# 16_HDMI_schdoc.net
KiCad netlist of a schematic drawn in Altium Designer
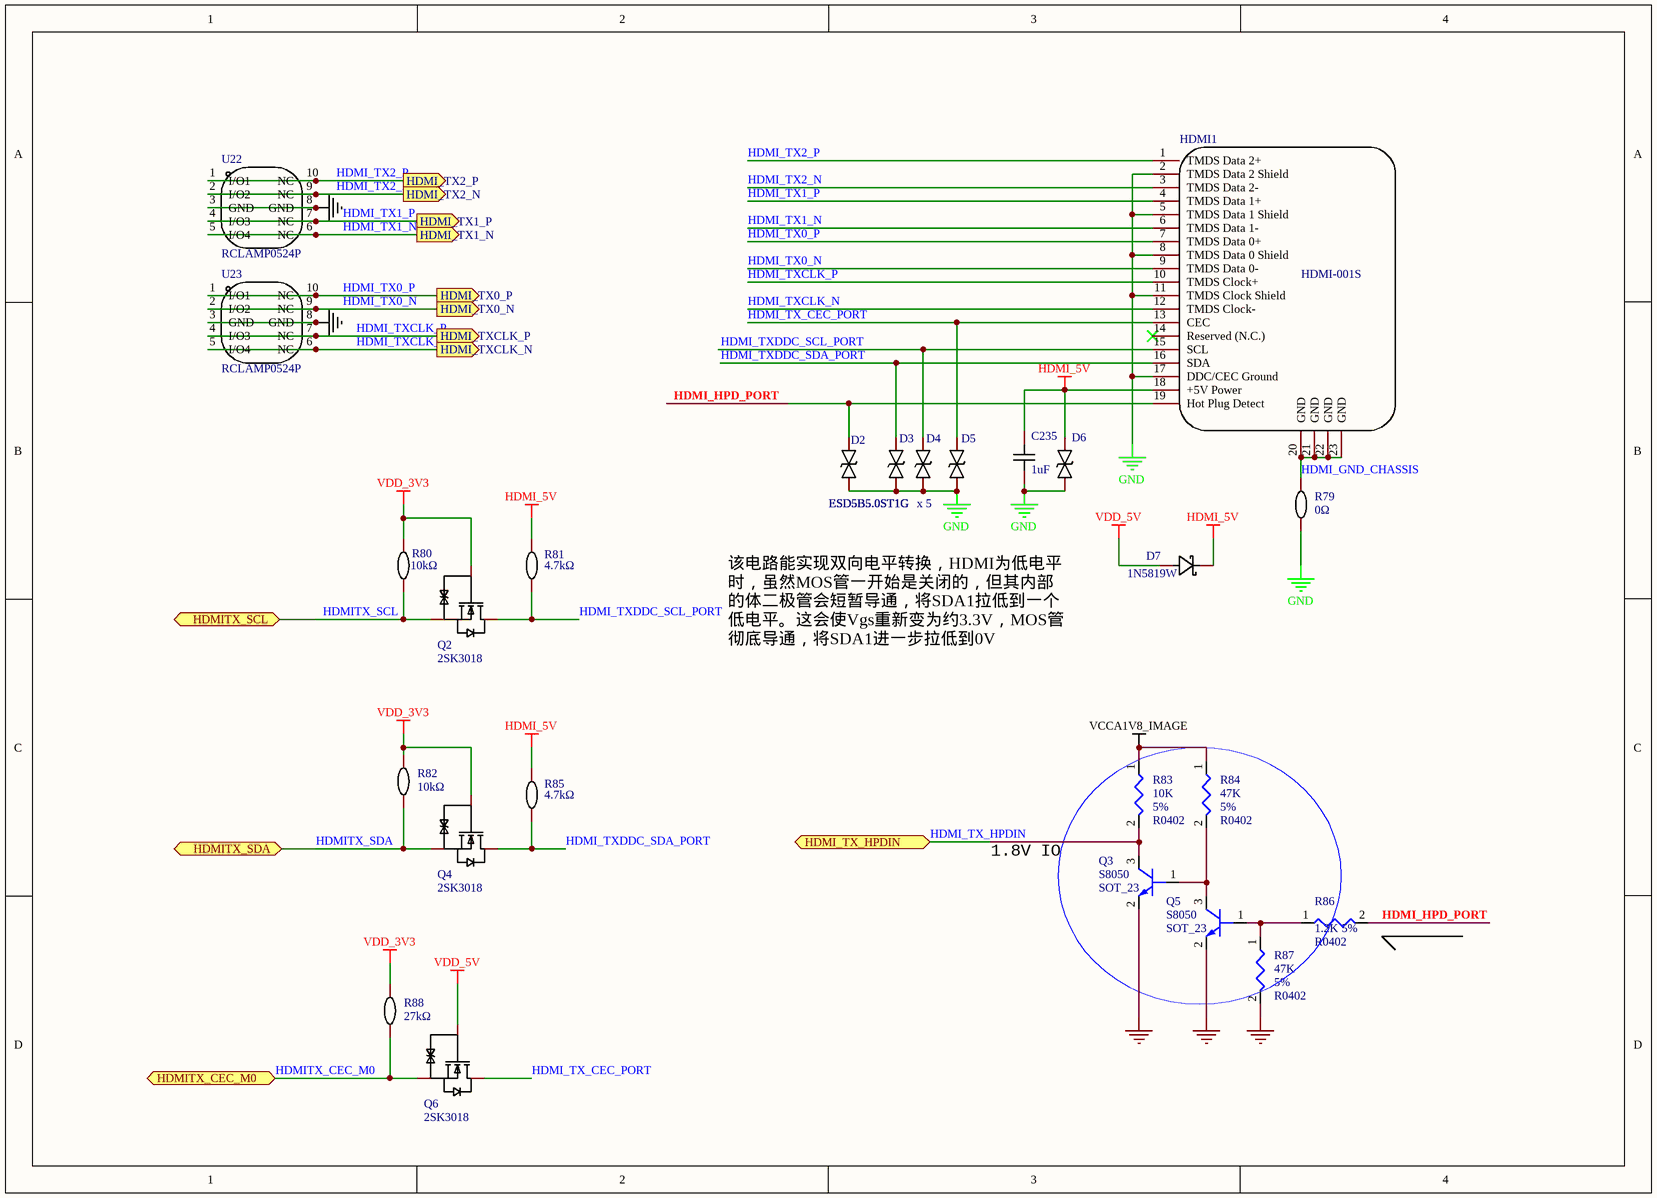
[diagram p0: 16_HDMI接口.schdoc.schdoc]

(export (version "E")
  (design (tool "Eeschema 10.0.6"))
  (components
    (comp (ref "C235")
      (value "1uF")
      (footprint "C0603")
      (fields
        (field (name "NAME") "1uF")
        (field (name "MANUFACTURER") "SAMSUNG(三星)")
        (field (name "MANUFACTURER PART") "CL10A105KB8NNNC")
        (field (name "TOLERANCE") "±10%")
      )
      (libsource (lib "altium-import") (part "root_1_CL10A105KB8NNNC_"))
    )
    (comp (ref "D2")
      (value "ESD5B5.0ST1G")
      (footprint "SOD-523_L1.2-W0.8-LS1.6-BI")
      (fields (field (name "NAME") "ESD5B5.0ST1G") (field (name "MANUFACTURER") "onsemi(安森美)"))
      (libsource (lib "altium-import") (part "root_1_ESD5B5.0ST1G_"))
    )
    (comp (ref "D3")
      (value "ESD5B5.0ST1G")
      (footprint "SOD-523_L1.2-W0.8-LS1.6-BI")
      (fields (field (name "NAME") "ESD5B5.0ST1G") (field (name "MANUFACTURER") "onsemi(安森美)"))
      (libsource (lib "altium-import") (part "root_1_ESD5B5.0ST1G_"))
    )
    (comp (ref "D4")
      (value "ESD5B5.0ST1G")
      (footprint "SOD-523_L1.2-W0.8-LS1.6-BI")
      (fields (field (name "NAME") "ESD5B5.0ST1G") (field (name "MANUFACTURER") "onsemi(安森美)"))
      (libsource (lib "altium-import") (part "root_1_ESD5B5.0ST1G_"))
    )
    (comp (ref "D5")
      (value "ESD5B5.0ST1G")
      (footprint "SOD-523_L1.2-W0.8-LS1.6-BI")
      (fields (field (name "NAME") "ESD5B5.0ST1G") (field (name "MANUFACTURER") "onsemi(安森美)"))
      (libsource (lib "altium-import") (part "root_1_ESD5B5.0ST1G_"))
    )
    (comp (ref "D6")
      (value "ESD5B5.0ST1G")
      (footprint "SOD-523_L1.2-W0.8-LS1.6-BI")
      (fields (field (name "NAME") "ESD5B5.0ST1G") (field (name "MANUFACTURER") "onsemi(安森美)"))
      (libsource (lib "altium-import") (part "root_1_ESD5B5.0ST1G_"))
    )
    (comp (ref "D7")
      (value "1N5819W")
      (footprint "SOD-123_L2.7-W1.6-LS3.7-R-RD")
      (fields (field (name "NAME") "1N5819W") (field (name "MANUFACTURER") "JSMSEMI(杰盛微)"))
      (libsource (lib "altium-import") (part "root_2_1N5819W_C963381_"))
    )
    (comp (ref "HDMI1")
      (value "HDMI-001S")
      (footprint "HDMI-SMD_HDMI-001S")
      (fields (field (name "NAME") "HDMI-001S") (field (name "MANUFACTURER") "XUNPU(讯普)"))
      (libsource (lib "altium-import") (part "root_0_HDMI-001S_"))
    )
    (comp (ref "Q2")
      (value "2SK3018")
      (footprint "SOT-23-3_L2.9-W1.4-P1.90-LS2.6-BR")
      (fields (field (name "NAME") "2SK3018") (field (name "MANUFACTURER") "TWGMC(台湾迪嘉)"))
      (libsource (lib "altium-import") (part "root_3_2SK3018_"))
    )
    (comp (ref "Q3")
      (value "S8050")
      (footprint "SOT_23")
      (description "S8050,SOT23")
      (fields
        (field (name "PCB FOOTPRINT") "SOT_23")
        (field (name "MANUFACTURER") "长电")
        (field (name "CREATED BY") "JJJ")
      )
      (libsource (lib "*") (part "NPN"))
    )
    (comp (ref "Q4")
      (value "2SK3018")
      (footprint "SOT-23-3_L2.9-W1.4-P1.90-LS2.6-BR")
      (fields (field (name "NAME") "2SK3018") (field (name "MANUFACTURER") "TWGMC(台湾迪嘉)"))
      (libsource (lib "altium-import") (part "root_3_2SK3018_"))
    )
    (comp (ref "Q5")
      (value "S8050")
      (footprint "SOT_23")
      (description "S8050,SOT23")
      (fields
        (field (name "PCB FOOTPRINT") "SOT_23")
        (field (name "MANUFACTURER") "长电")
        (field (name "CREATED BY") "JJJ")
      )
      (libsource (lib "*") (part "NPN"))
    )
    (comp (ref "Q6")
      (value "2SK3018")
      (footprint "SOT-23-3_L2.9-W1.4-P1.90-LS2.6-BR")
      (fields (field (name "NAME") "2SK3018") (field (name "MANUFACTURER") "TWGMC(台湾迪嘉)"))
      (libsource (lib "altium-import") (part "root_3_2SK3018_"))
    )
    (comp (ref "R79")
      (value "0Ω")
      (footprint "R0603")
      (fields
        (field (name "NAME") "0Ω")
        (field (name "MANUFACTURER") "UNI-ROYAL(厚声)")
        (field (name "MANUFACTURER PART") "0603WAF0000T5E")
        (field (name "TOLERANCE") "±1%")
      )
      (libsource (lib "altium-import") (part "root_1_0603WAF0000T5E_"))
    )
    (comp (ref "R80")
      (value "10kΩ")
      (footprint "R0603")
      (fields
        (field (name "NAME") "10kΩ")
        (field (name "MANUFACTURER") "UNI-ROYAL(厚声)")
        (field (name "MANUFACTURER PART") "0603WAF1002T5E")
        (field (name "TOLERANCE") "±1%")
      )
      (libsource (lib "altium-import") (part "root_1_0603WAF1002T5E_"))
    )
    (comp (ref "R81")
      (value "4.7kΩ")
      (footprint "R0603")
      (fields
        (field (name "NAME") "4.7kΩ")
        (field (name "MANUFACTURER") "UNI-ROYAL(厚声)")
        (field (name "MANUFACTURER PART") "0603WAF4701T5E")
        (field (name "TOLERANCE") "±1%")
      )
      (libsource (lib "altium-import") (part "root_1_0603WAF4701T5E_"))
    )
    (comp (ref "R82")
      (value "10kΩ")
      (footprint "R0603")
      (fields
        (field (name "NAME") "10kΩ")
        (field (name "MANUFACTURER") "UNI-ROYAL(厚声)")
        (field (name "MANUFACTURER PART") "0603WAF1002T5E")
        (field (name "TOLERANCE") "±1%")
      )
      (libsource (lib "altium-import") (part "root_1_0603WAF1002T5E_"))
    )
    (comp (ref "R83")
      (value "10K")
      (footprint "R0402")
      (description "通用厚膜电阻,10K,+/-5%,R0402,1/16W.")
      (fields
        (field (name "PCB FOOTPRINT") "R0402")
        (field (name "TOLERANCE") "5%")
        (field (name "MANUFACTURER") "YAGEO")
        (field (name "CREATED BY") "YTL")
      )
      (libsource (lib "*") (part "RESISTOR_Dup1"))
    )
    (comp (ref "R84")
      (value "47K")
      (footprint "R0402")
      (description "通用厚膜电阻,47K,+/-5%,R0402,1/16W.")
      (fields
        (field (name "PCB FOOTPRINT") "R0402")
        (field (name "TOLERANCE") "5%")
        (field (name "MANUFACTURER") "YAGEO")
        (field (name "CREATED BY") "YTL")
      )
      (libsource (lib "*") (part "RESISTOR_Dup1"))
    )
    (comp (ref "R85")
      (value "4.7kΩ")
      (footprint "R0603")
      (fields
        (field (name "NAME") "4.7kΩ")
        (field (name "MANUFACTURER") "UNI-ROYAL(厚声)")
        (field (name "MANUFACTURER PART") "0603WAF4701T5E")
        (field (name "TOLERANCE") "±1%")
      )
      (libsource (lib "altium-import") (part "root_1_0603WAF4701T5E_"))
    )
    (comp (ref "R86")
      (value "1.2K")
      (footprint "R0402")
      (description "通用厚膜电阻,1K2,+/-5%,R0402,1/16W.")
      (fields
        (field (name "PCB FOOTPRINT") "R0402")
        (field (name "TOLERANCE") "5%")
        (field (name "MANUFACTURER") "YAGEO")
        (field (name "CREATED BY") "YTL")
      )
      (libsource (lib "*") (part "RESISTOR_Dup1"))
    )
    (comp (ref "R87")
      (value "47K")
      (footprint "R0402")
      (description "通用厚膜电阻,47K,+/-5%,R0402,1/16W.")
      (fields
        (field (name "PCB FOOTPRINT") "R0402")
        (field (name "TOLERANCE") "5%")
        (field (name "MANUFACTURER") "YAGEO")
        (field (name "CREATED BY") "YTL")
      )
      (libsource (lib "*") (part "RESISTOR_Dup1"))
    )
    (comp (ref "R88")
      (value "27kΩ")
      (footprint "R0603")
      (fields
        (field (name "NAME") "27kΩ")
        (field (name "MANUFACTURER") "UNI-ROYAL(厚声)")
        (field (name "MANUFACTURER PART") "0603WAF2702T5E")
        (field (name "TOLERANCE") "±1%")
      )
      (libsource (lib "altium-import") (part "root_1_0603WAF2702T5E_"))
    )
    (comp (ref "U22")
      (value "RCLAMP0524P")
      (footprint "DFN2510-10_L2.5-W1.0-P0.50-BL")
      (fields (field (name "NAME") "RCLAMP0524P") (field (name "MANUFACTURER") "TECH PUBLIC(台舟)"))
      (libsource (lib "altium-import") (part "root_0_RCLAMP0524P_C907837_"))
    )
    (comp (ref "U23")
      (value "RCLAMP0524P")
      (footprint "DFN2510-10_L2.5-W1.0-P0.50-BL")
      (fields (field (name "NAME") "RCLAMP0524P") (field (name "MANUFACTURER") "TECH PUBLIC(台舟)"))
      (libsource (lib "altium-import") (part "root_0_RCLAMP0524P_C907837_"))
    )
  )
  (nets
    (net (code "1") (name "/HDMITX_CEC_M0") (class "Default")
      (node (ref "Q6") (pin "2") (pinfunction "S_2") (pintype "passive"))
      (node (ref "R88") (pin "1") (pinfunction "1_1") (pintype "passive"))
    )
    (net (code "2") (name "/HDMITX_SCL") (class "Default")
      (node (ref "Q2") (pin "2") (pinfunction "S_2") (pintype "passive"))
      (node (ref "R80") (pin "1") (pinfunction "1_1") (pintype "passive"))
    )
    (net (code "3") (name "/HDMITX_SDA") (class "Default")
      (node (ref "Q4") (pin "2") (pinfunction "S_2") (pintype "passive"))
      (node (ref "R82") (pin "1") (pinfunction "1_1") (pintype "passive"))
    )
    (net (code "4") (name "/HDMI_GND_CHASSIS") (class "Default")
      (node (ref "HDMI1") (pin "20") (pinfunction "GND_20") (pintype "passive"))
      (node (ref "HDMI1") (pin "21") (pinfunction "GND_21") (pintype "passive"))
      (node (ref "HDMI1") (pin "22") (pinfunction "GND_22") (pintype "passive"))
      (node (ref "HDMI1") (pin "23") (pinfunction "GND_23") (pintype "passive"))
      (node (ref "R79") (pin "2") (pinfunction "2_2") (pintype "passive"))
    )
    (net (code "5") (name "/HDMI_HPD_PORT") (class "Default")
      (node (ref "D2") (pin "2") (pinfunction "2_2") (pintype "passive"))
      (node (ref "HDMI1") (pin "19") (pinfunction "Hot_Plug_Detect_19") (pintype "passive"))
      (node (ref "R86") (pin "2") (pinfunction "2_2") (pintype "passive"))
    )
    (net (code "6") (name "/HDMI_TX0_N") (class "Default")
      (node (ref "HDMI1") (pin "9") (pinfunction "TMDS_Data_0-_9") (pintype "passive"))
      (node (ref "U23") (pin "2") (pinfunction "I/O2_2") (pintype "passive"))
      (node (ref "U23") (pin "9") (pinfunction "NC_9") (pintype "passive"))
    )
    (net (code "7") (name "/HDMI_TX0_P") (class "Default")
      (node (ref "HDMI1") (pin "7") (pinfunction "TMDS_Data_0+_7") (pintype "passive"))
      (node (ref "U23") (pin "1") (pinfunction "I/O1_1") (pintype "passive"))
      (node (ref "U23") (pin "10") (pinfunction "NC_10") (pintype "passive"))
    )
    (net (code "8") (name "/HDMI_TX1_N") (class "Default")
      (node (ref "HDMI1") (pin "6") (pinfunction "TMDS_Data_1-_6") (pintype "passive"))
      (node (ref "U22") (pin "5") (pinfunction "I/O4_5") (pintype "passive"))
      (node (ref "U22") (pin "6") (pinfunction "NC_6") (pintype "passive"))
    )
    (net (code "9") (name "/HDMI_TX1_P") (class "Default")
      (node (ref "HDMI1") (pin "4") (pinfunction "TMDS_Data_1+_4") (pintype "passive"))
      (node (ref "U22") (pin "4") (pinfunction "I/O3_4") (pintype "passive"))
      (node (ref "U22") (pin "7") (pinfunction "NC_7") (pintype "passive"))
    )
    (net (code "10") (name "/HDMI_TX2_N") (class "Default")
      (node (ref "HDMI1") (pin "3") (pinfunction "TMDS_Data_2-_3") (pintype "passive"))
      (node (ref "U22") (pin "2") (pinfunction "I/O2_2") (pintype "passive"))
      (node (ref "U22") (pin "9") (pinfunction "NC_9") (pintype "passive"))
    )
    (net (code "11") (name "/HDMI_TX2_P") (class "Default")
      (node (ref "HDMI1") (pin "1") (pinfunction "TMDS_Data_2+_1") (pintype "passive"))
      (node (ref "U22") (pin "1") (pinfunction "I/O1_1") (pintype "passive"))
      (node (ref "U22") (pin "10") (pinfunction "NC_10") (pintype "passive"))
    )
    (net (code "12") (name "/HDMI_TXCLK_N") (class "Default")
      (node (ref "HDMI1") (pin "12") (pinfunction "TMDS_Clock-_12") (pintype "passive"))
      (node (ref "U23") (pin "5") (pinfunction "I/O4_5") (pintype "passive"))
      (node (ref "U23") (pin "6") (pinfunction "NC_6") (pintype "passive"))
    )
    (net (code "13") (name "/HDMI_TXCLK_P") (class "Default")
      (node (ref "HDMI1") (pin "10") (pinfunction "TMDS_Clock+_10") (pintype "passive"))
      (node (ref "U23") (pin "4") (pinfunction "I/O3_4") (pintype "passive"))
      (node (ref "U23") (pin "7") (pinfunction "NC_7") (pintype "passive"))
    )
    (net (code "14") (name "/HDMI_TXDDC_SCL_PORT") (class "Default")
      (node (ref "D4") (pin "2") (pinfunction "2_2") (pintype "passive"))
      (node (ref "HDMI1") (pin "15") (pinfunction "SCL_15") (pintype "passive"))
      (node (ref "Q2") (pin "3") (pinfunction "D_3") (pintype "passive"))
      (node (ref "R81") (pin "1") (pinfunction "1_1") (pintype "passive"))
    )
    (net (code "15") (name "/HDMI_TXDDC_SDA_PORT") (class "Default")
      (node (ref "D3") (pin "2") (pinfunction "2_2") (pintype "passive"))
      (node (ref "HDMI1") (pin "16") (pinfunction "SDA_16") (pintype "passive"))
      (node (ref "Q4") (pin "3") (pinfunction "D_3") (pintype "passive"))
      (node (ref "R85") (pin "1") (pinfunction "1_1") (pintype "passive"))
    )
    (net (code "16") (name "/HDMI_TX_CEC_PORT") (class "Default")
      (node (ref "D5") (pin "2") (pinfunction "2_2") (pintype "passive"))
      (node (ref "HDMI1") (pin "13") (pinfunction "CEC_13") (pintype "passive"))
      (node (ref "Q6") (pin "3") (pinfunction "D_3") (pintype "passive"))
    )
    (net (code "17") (name "/HDMI_TX_HPDIN") (class "Default")
      (node (ref "Q3") (pin "3") (pinfunction "COLLECTOR_3") (pintype "passive"))
      (node (ref "R83") (pin "2") (pinfunction "2_2") (pintype "passive"))
    )
    (net (code "18") (name "GND") (class "Default")
      (node (ref "C235") (pin "1") (pinfunction "1_1") (pintype "passive"))
      (node (ref "D2") (pin "1") (pinfunction "1_1") (pintype "passive"))
      (node (ref "D3") (pin "1") (pinfunction "1_1") (pintype "passive"))
      (node (ref "D4") (pin "1") (pinfunction "1_1") (pintype "passive"))
      (node (ref "D5") (pin "1") (pinfunction "1_1") (pintype "passive"))
      (node (ref "D6") (pin "1") (pinfunction "1_1") (pintype "passive"))
      (node (ref "HDMI1") (pin "11") (pinfunction "TMDS_Clock_Shield_11") (pintype "passive"))
      (node (ref "HDMI1") (pin "17") (pinfunction "DDC/CEC_Ground_17") (pintype "passive"))
      (node (ref "HDMI1") (pin "2") (pinfunction "TMDS_Data_2_Shield_2") (pintype "passive"))
      (node (ref "HDMI1") (pin "5") (pinfunction "TMDS_Data_1_Shield_5") (pintype "passive"))
      (node (ref "HDMI1") (pin "8") (pinfunction "TMDS_Data_0_Shield_8") (pintype "passive"))
      (node (ref "Q3") (pin "2") (pinfunction "EMITTER_2") (pintype "passive"))
      (node (ref "Q5") (pin "2") (pinfunction "EMITTER_2") (pintype "passive"))
      (node (ref "R79") (pin "1") (pinfunction "1_1") (pintype "passive"))
      (node (ref "R87") (pin "2") (pinfunction "2_2") (pintype "passive"))
      (node (ref "U22") (pin "3") (pinfunction "GND_3") (pintype "passive"))
      (node (ref "U22") (pin "8") (pinfunction "GND_8") (pintype "passive"))
      (node (ref "U23") (pin "3") (pinfunction "GND_3") (pintype "passive"))
      (node (ref "U23") (pin "8") (pinfunction "GND_8") (pintype "passive"))
    )
    (net (code "19") (name "HDMI_5V") (class "Default")
      (node (ref "C235") (pin "2") (pinfunction "2_2") (pintype "passive"))
      (node (ref "D6") (pin "2") (pinfunction "2_2") (pintype "passive"))
      (node (ref "D7") (pin "2") (pinfunction "C_2") (pintype "passive"))
      (node (ref "HDMI1") (pin "18") (pinfunction "+5V_Power_18") (pintype "passive"))
      (node (ref "R81") (pin "2") (pinfunction "2_2") (pintype "passive"))
      (node (ref "R85") (pin "2") (pinfunction "2_2") (pintype "passive"))
    )
    (net (code "20") (name "Net-(Q3-BASE)") (class "Default")
      (node (ref "Q3") (pin "1") (pinfunction "BASE_1") (pintype "passive"))
      (node (ref "Q5") (pin "3") (pinfunction "COLLECTOR_3") (pintype "passive"))
      (node (ref "R84") (pin "2") (pinfunction "2_2") (pintype "passive"))
    )
    (net (code "21") (name "Net-(Q5-BASE)") (class "Default")
      (node (ref "Q5") (pin "1") (pinfunction "BASE_1") (pintype "passive"))
      (node (ref "R86") (pin "1") (pinfunction "1_1") (pintype "passive"))
      (node (ref "R87") (pin "1") (pinfunction "1_1") (pintype "passive"))
    )
    (net (code "22") (name "VCCA1V8_IMAGE") (class "Default")
      (node (ref "R83") (pin "1") (pinfunction "1_1") (pintype "passive"))
      (node (ref "R84") (pin "1") (pinfunction "1_1") (pintype "passive"))
    )
    (net (code "23") (name "VDD_3V3") (class "Default")
      (node (ref "Q2") (pin "1") (pinfunction "G_1") (pintype "passive"))
      (node (ref "Q4") (pin "1") (pinfunction "G_1") (pintype "passive"))
      (node (ref "R80") (pin "2") (pinfunction "2_2") (pintype "passive"))
      (node (ref "R82") (pin "2") (pinfunction "2_2") (pintype "passive"))
      (node (ref "R88") (pin "2") (pinfunction "2_2") (pintype "passive"))
    )
    (net (code "24") (name "VDD_5V") (class "Default")
      (node (ref "D7") (pin "1") (pinfunction "A_1") (pintype "passive"))
      (node (ref "Q6") (pin "1") (pinfunction "G_1") (pintype "passive"))
    )
    (net (code "25") (name "unconnected-(HDMI1-Reserved_(N.C.)-Pad14)") (class "Default")
      (node (ref "HDMI1") (pin "14") (pinfunction "Reserved_(N.C.)_14") (pintype "passive+no_connect"))
    )
  )
)
